# POWER.net
KiCad netlist of a schematic drawn in Altium Designer
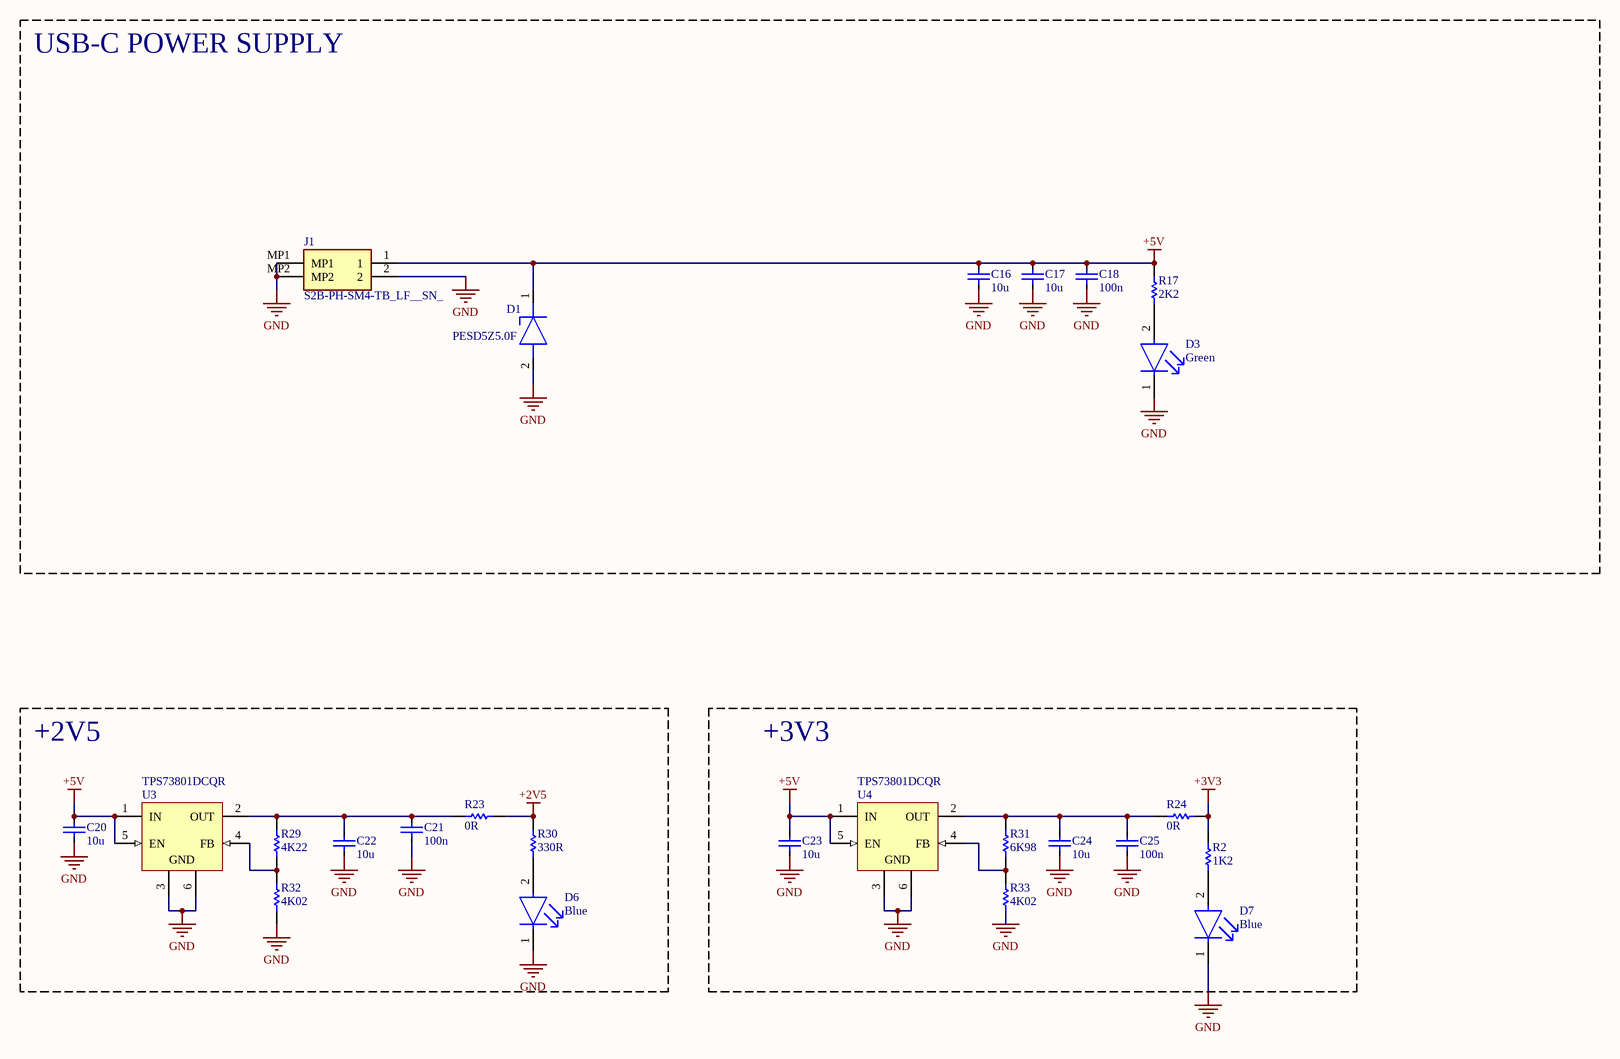
[diagram p0: POWER.SchDoc]

(export (version "E")
  (design (tool "Eeschema 10.0.6"))
  (components
    (comp (ref "C16")
      (value "10u")
      (footprint "FP-C1608-080-0_1-IPC_C")
      (description "MLCC 10μF ±10% 6.3V JB SMD 0603")
      (fields (field (name "TOLERANCE") "10%") (field (name "Comment") "C1608JB0J106K080AB"))
      (libsource (lib "Schlib1") (part "C1608JB0J106K080AB"))
    )
    (comp (ref "C17")
      (value "10u")
      (footprint "FP-C1608-080-0_1-IPC_C")
      (description "MLCC 10μF ±10% 6.3V JB SMD 0603")
      (fields (field (name "TOLERANCE") "10%") (field (name "Comment") "C1608JB0J106K080AB"))
      (libsource (lib "Schlib1") (part "C1608JB0J106K080AB"))
    )
    (comp (ref "C18")
      (value "100n")
      (footprint "FP-C1005-050-0_05-IPC_C")
      (description "MLCC 100nF ±10% 50V X7R SMD 0402")
      (fields (field (name "VOLTAGE") "50V") (field (name "TOLERANCE") "10%"))
      (libsource (lib "Schlib1") (part "C1005X7R1H104K050BB"))
    )
    (comp (ref "C20")
      (value "10u")
      (footprint "FP-C1608-080-0_1-IPC_C")
      (description "MLCC 10μF ±10% 6.3V JB SMD 0603")
      (fields (field (name "TOLERANCE") "10%") (field (name "Comment") "C1608JB0J106K080AB"))
      (libsource (lib "Schlib1") (part "C1608JB0J106K080AB"))
    )
    (comp (ref "C21")
      (value "100n")
      (footprint "FP-C1005-050-0_05-IPC_C")
      (description "MLCC 100nF ±10% 50V X7R SMD 0402")
      (fields (field (name "VOLTAGE") "50V") (field (name "TOLERANCE") "10%"))
      (libsource (lib "Schlib1") (part "C1005X7R1H104K050BB"))
    )
    (comp (ref "C22")
      (value "10u")
      (footprint "FP-C1608-080-0_1-IPC_C")
      (description "MLCC 10μF ±10% 6.3V JB SMD 0603")
      (fields (field (name "TOLERANCE") "10%") (field (name "Comment") "C1608JB0J106K080AB"))
      (libsource (lib "Schlib1") (part "C1608JB0J106K080AB"))
    )
    (comp (ref "C23")
      (value "10u")
      (footprint "FP-C1608-080-0_1-IPC_C")
      (description "MLCC 10μF ±10% 6.3V JB SMD 0603")
      (fields (field (name "TOLERANCE") "10%") (field (name "Comment") "C1608JB0J106K080AB"))
      (libsource (lib "Schlib1") (part "C1608JB0J106K080AB"))
    )
    (comp (ref "C24")
      (value "10u")
      (footprint "FP-C1608-080-0_1-IPC_C")
      (description "MLCC 10μF ±10% 6.3V JB SMD 0603")
      (fields (field (name "TOLERANCE") "10%") (field (name "Comment") "C1608JB0J106K080AB"))
      (libsource (lib "Schlib1") (part "C1608JB0J106K080AB"))
    )
    (comp (ref "C25")
      (value "100n")
      (footprint "FP-C1005-050-0_05-IPC_C")
      (description "MLCC 100nF ±10% 50V X7R SMD 0402")
      (fields (field (name "VOLTAGE") "50V") (field (name "TOLERANCE") "10%"))
      (libsource (lib "Schlib1") (part "C1005X7R1H104K050BB"))
    )
    (comp (ref "D1")
      (value "PESD5Z5.0F")
      (footprint "SamacSys:SODFL1608X65N")
      (description "Diode ESD (Uni-directional)")
      (fields (field (name "MOUSER PART NUMBER") "771-PESD5Z5.0F"))
      (libsource (lib "*") (part "PESD5Z5.0F"))
    )
    (comp (ref "D3")
      (value "LTST-C191GKT")
      (footprint "FP-LTST-C191GKT-MFG")
      (description "LED GREEN CLEAR CHIP SMD")
      (fields (field (name "COLOR") "Green"))
      (libsource (lib "Altium Content Vault") (part "8706943c75ba83719d021d2fdc84c58"))
    )
    (comp (ref "D6")
      (value "LTST-C191TBKT")
      (footprint "FP-LTST-C191TBKT-MFG")
      (description "LED BLUE CLEAR CHIP SMD")
      (fields (field (name "COLOR") "Blue"))
      (libsource (lib "Altium Content Vault") (part "8706943c75ba83719d021d2fdc84c58"))
    )
    (comp (ref "D7")
      (value "LTST-C191TBKT")
      (footprint "FP-LTST-C191TBKT-MFG")
      (description "LED BLUE CLEAR CHIP SMD")
      (fields (field (name "COLOR") "Blue"))
      (libsource (lib "Altium Content Vault") (part "8706943c75ba83719d021d2fdc84c58"))
    )
    (comp (ref "J1")
      (value "S2B-PH-SM4-TB_LF__SN_")
      (footprint "SamacSys:S2BPHSM4TBLFSN")
      (description "Connector")
      (fields (field (name "MANUFACTURER_PART_NUMBER") "S2B-PH-SM4-TB(LF)(SN)"))
      (libsource (lib "*") (part "S2B-PH-SM4-TB_LF__SN_"))
    )
    (comp (ref "R2")
      (value "1K2")
      (footprint "RESC1005X40X25ML05T10")
      (fields (field (name "PART NUMBER") "RC0402FR-071K2L") (field (name "MANUFACTURER") "Yageo / Phycomp"))
      (libsource (lib "Altium Content Vault") (part "RES"))
    )
    (comp (ref "R17")
      (value "2K2")
      (footprint "RESC1005X40X25NL05T10")
      (fields (field (name "MANUFACTURER") "Yageo / Phycomp") (field (name "PART NUMBER") "RC0402FR-072K2L"))
      (libsource (lib "Altium Content Vault") (part "RES"))
    )
    (comp (ref "R23")
      (value "0R")
      (footprint "RESC1005X40X25NL05T10")
      (fields
        (field (name "MANUFACTURER") "Yageo / Phycomp")
        (field (name "PART NUMBER") "RC0402FR-076K98L")
        (field (name "Comment") "RC0402FR-070RL")
      )
      (libsource (lib "Schlib1") (part "RC0402FR-070RL"))
    )
    (comp (ref "R24")
      (value "0R")
      (footprint "RESC1005X40X25NL05T10")
      (fields
        (field (name "MANUFACTURER") "Yageo / Phycomp")
        (field (name "PART NUMBER") "RC0402FR-076K98L")
        (field (name "Comment") "RC0402FR-070RL")
      )
      (libsource (lib "Schlib1") (part "RC0402FR-070RL"))
    )
    (comp (ref "R29")
      (value "4K22")
      (footprint "RESC1005X40X25ML05T10")
      (fields (field (name "PART NUMBER") "RC0402FR-074K22L") (field (name "MANUFACTURER") "Yageo / Phycomp"))
      (libsource (lib "Altium Content Vault") (part "RES"))
    )
    (comp (ref "R30")
      (value "330R")
      (footprint "RESC1005X40X25ML05T10")
      (fields (field (name "PART NUMBER") "RC0402FR-07330RL") (field (name "MANUFACTURER") "Yageo / Phycomp"))
      (libsource (lib "Altium Content Vault") (part "RES"))
    )
    (comp (ref "R31")
      (value "6K98")
      (footprint "RESC1005X40X25ML05T10")
      (fields (field (name "MANUFACTURER") "Yageo / Phycomp") (field (name "PART NUMBER") "RC0402FR-076K98L"))
      (libsource (lib "Altium Content Vault") (part "RES"))
    )
    (comp (ref "R32")
      (value "4K02")
      (footprint "RESC1005X40X25ML05T10")
      (fields (field (name "MANUFACTURER") "Yageo / Phycomp") (field (name "PART NUMBER") "RC0402FR-074K02L"))
      (libsource (lib "Altium Content Vault") (part "RES"))
    )
    (comp (ref "R33")
      (value "4K02")
      (footprint "RESC1005X40X25ML05T10")
      (fields (field (name "MANUFACTURER") "Yageo / Phycomp") (field (name "PART NUMBER") "RC0402FR-074K02L"))
      (libsource (lib "Altium Content Vault") (part "RES"))
    )
    (comp (ref "U3")
      (value "TPS73801DCQR")
      (footprint "DCQ0006A_L")
      (fields (field (name "MANUFACTURER") "Texas Instruments"))
      (libsource (lib "Altium Content Vault") (part "TI-TPS73X01-DCQ6"))
    )
    (comp (ref "U4")
      (value "TPS73801DCQR")
      (footprint "DCQ0006A_L")
      (fields (field (name "MANUFACTURER") "Texas Instruments"))
      (libsource (lib "Altium Content Vault") (part "TI-TPS73X01-DCQ6"))
    )
  )
  (nets
    (net (code "1") (name "+2V5") (class "Default")
      (node (ref "R23") (pin "1") (pinfunction "1_1") (pintype "passive"))
      (node (ref "R30") (pin "1") (pinfunction "1_1") (pintype "passive"))
    )
    (net (code "2") (name "+3V3") (class "Default")
      (node (ref "R2") (pin "1") (pinfunction "1_1") (pintype "passive"))
      (node (ref "R24") (pin "1") (pinfunction "1_1") (pintype "passive"))
    )
    (net (code "3") (name "+5V") (class "Default")
      (node (ref "C16") (pin "1") (pinfunction "1_1") (pintype "passive"))
      (node (ref "C17") (pin "1") (pinfunction "1_1") (pintype "passive"))
      (node (ref "C18") (pin "1") (pinfunction "1_1") (pintype "passive"))
      (node (ref "C20") (pin "1") (pinfunction "1_1") (pintype "passive"))
      (node (ref "C23") (pin "1") (pinfunction "1_1") (pintype "passive"))
      (node (ref "D1") (pin "1") (pinfunction "K_1") (pintype "passive"))
      (node (ref "J1") (pin "1") (pinfunction "1_1") (pintype "passive"))
      (node (ref "R17") (pin "1") (pinfunction "1_1") (pintype "passive"))
      (node (ref "U3") (pin "1") (pinfunction "IN_1") (pintype "power_in"))
      (node (ref "U3") (pin "5") (pinfunction "EN_5") (pintype "input"))
      (node (ref "U4") (pin "1") (pinfunction "IN_1") (pintype "power_in"))
      (node (ref "U4") (pin "5") (pinfunction "EN_5") (pintype "input"))
    )
    (net (code "4") (name "GND") (class "Default")
      (node (ref "C16") (pin "2") (pinfunction "2_2") (pintype "passive"))
      (node (ref "C17") (pin "2") (pinfunction "2_2") (pintype "passive"))
      (node (ref "C18") (pin "2") (pinfunction "2_2") (pintype "passive"))
      (node (ref "C20") (pin "2") (pinfunction "2_2") (pintype "passive"))
      (node (ref "C21") (pin "2") (pinfunction "2_2") (pintype "passive"))
      (node (ref "C22") (pin "2") (pinfunction "2_2") (pintype "passive"))
      (node (ref "C23") (pin "2") (pinfunction "2_2") (pintype "passive"))
      (node (ref "C24") (pin "2") (pinfunction "2_2") (pintype "passive"))
      (node (ref "C25") (pin "2") (pinfunction "2_2") (pintype "passive"))
      (node (ref "D1") (pin "2") (pinfunction "A_2") (pintype "passive"))
      (node (ref "D3") (pin "1") (pinfunction "C_1") (pintype "passive"))
      (node (ref "D6") (pin "1") (pinfunction "C_1") (pintype "passive"))
      (node (ref "D7") (pin "1") (pinfunction "C_1") (pintype "passive"))
      (node (ref "J1") (pin "2") (pinfunction "2_2") (pintype "passive"))
      (node (ref "J1") (pin "MP1") (pinfunction "MP1_MP1") (pintype "passive"))
      (node (ref "J1") (pin "MP2") (pinfunction "MP2_MP2") (pintype "passive"))
      (node (ref "R32") (pin "1") (pinfunction "1_1") (pintype "passive"))
      (node (ref "R33") (pin "1") (pinfunction "1_1") (pintype "passive"))
      (node (ref "U3") (pin "3") (pinfunction "GND_3") (pintype "power_in"))
      (node (ref "U3") (pin "6") (pinfunction "GND_6") (pintype "power_in"))
      (node (ref "U4") (pin "3") (pinfunction "GND_3") (pintype "power_in"))
      (node (ref "U4") (pin "6") (pinfunction "GND_6") (pintype "power_in"))
    )
    (net (code "5") (name "Net-(D3-A)") (class "Default")
      (node (ref "D3") (pin "2") (pinfunction "A_2") (pintype "passive"))
      (node (ref "R17") (pin "2") (pinfunction "2_2") (pintype "passive"))
    )
    (net (code "6") (name "Net-(D6-A)") (class "Default")
      (node (ref "D6") (pin "2") (pinfunction "A_2") (pintype "passive"))
      (node (ref "R30") (pin "2") (pinfunction "2_2") (pintype "passive"))
    )
    (net (code "7") (name "Net-(D7-A)") (class "Default")
      (node (ref "D7") (pin "2") (pinfunction "A_2") (pintype "passive"))
      (node (ref "R2") (pin "2") (pinfunction "2_2") (pintype "passive"))
    )
    (net (code "8") (name "Net-(U3-FB)") (class "Default")
      (node (ref "R29") (pin "2") (pinfunction "2_2") (pintype "passive"))
      (node (ref "R32") (pin "2") (pinfunction "2_2") (pintype "passive"))
      (node (ref "U3") (pin "4") (pinfunction "FB_4") (pintype "input"))
    )
    (net (code "9") (name "Net-(U3-OUT)") (class "Default")
      (node (ref "C21") (pin "1") (pinfunction "1_1") (pintype "passive"))
      (node (ref "C22") (pin "1") (pinfunction "1_1") (pintype "passive"))
      (node (ref "R23") (pin "2") (pinfunction "2_2") (pintype "passive"))
      (node (ref "R29") (pin "1") (pinfunction "1_1") (pintype "passive"))
      (node (ref "U3") (pin "2") (pinfunction "OUT_2") (pintype "power_in"))
    )
    (net (code "10") (name "Net-(U4-FB)") (class "Default")
      (node (ref "R31") (pin "1") (pinfunction "1_1") (pintype "passive"))
      (node (ref "R33") (pin "2") (pinfunction "2_2") (pintype "passive"))
      (node (ref "U4") (pin "4") (pinfunction "FB_4") (pintype "input"))
    )
    (net (code "11") (name "Net-(U4-OUT)") (class "Default")
      (node (ref "C24") (pin "1") (pinfunction "1_1") (pintype "passive"))
      (node (ref "C25") (pin "1") (pinfunction "1_1") (pintype "passive"))
      (node (ref "R24") (pin "2") (pinfunction "2_2") (pintype "passive"))
      (node (ref "R31") (pin "2") (pinfunction "2_2") (pintype "passive"))
      (node (ref "U4") (pin "2") (pinfunction "OUT_2") (pintype "power_in"))
    )
  )
)
